# 03_Sensing.net
KiCad netlist of a schematic drawn in Altium Designer
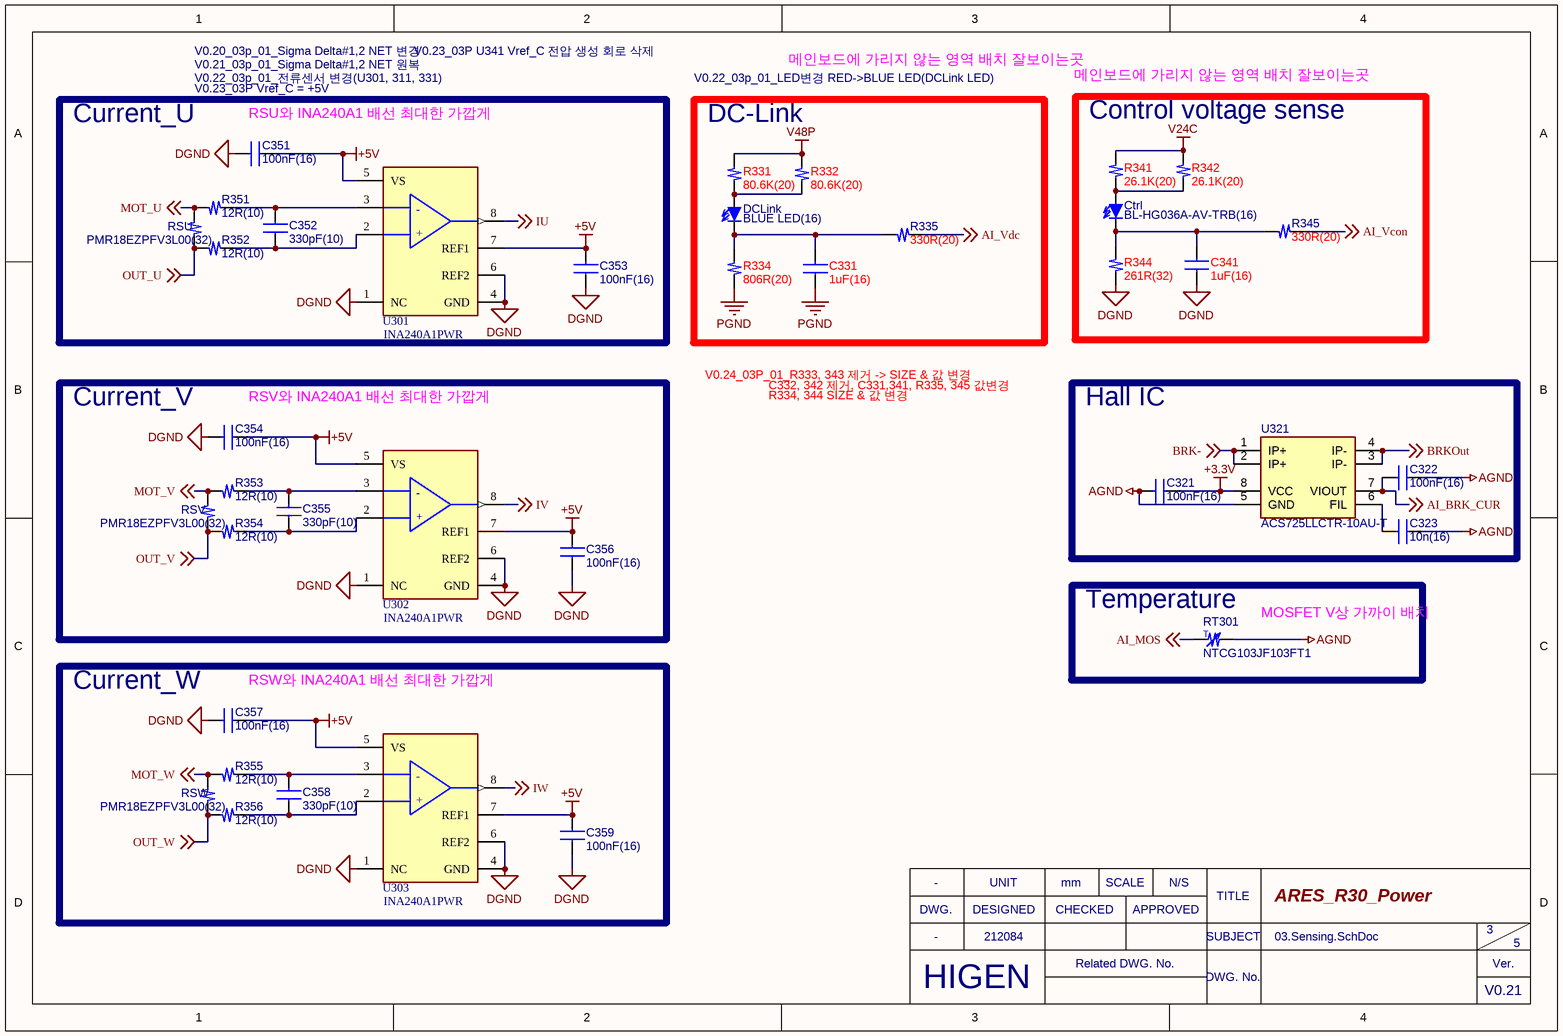
[diagram p0: 03.Sensing.SchDoc]

(export (version "E")
  (design (tool "Eeschema 10.0.6"))
  (components
    (comp (ref "C321") (value "100nF(16)") (footprint "C-1608S") (libsource (lib "HIGEN") (part "RES1")))
    (comp (ref "C322") (value "100nF(16)") (footprint "C-1608S") (libsource (lib "HIGEN") (part "RES1")))
    (comp (ref "C323") (value "10n(16)") (footprint "C-1608S") (libsource (lib "HIGEN") (part "Cap_NP")))
    (comp (ref "C331") (value "1uF(16)") (footprint "C-1608S") (libsource (lib "HIGEN") (part "RES1")))
    (comp (ref "C341") (value "1uF(16)") (footprint "C-1608S") (libsource (lib "HIGEN") (part "RES1")))
    (comp (ref "C351") (value "100nF(16)") (footprint "C-1608S") (libsource (lib "HIGEN") (part "RES1")))
    (comp (ref "C352") (value "330pF(10)") (footprint "C-1005S") (libsource (lib "HIGEN") (part "Cap_NP")))
    (comp (ref "C353") (value "100nF(16)") (footprint "C-1608") (libsource (lib "HIGEN") (part "Cap_NP")))
    (comp (ref "C354") (value "100nF(16)") (footprint "C-1608S") (libsource (lib "HIGEN") (part "RES1")))
    (comp (ref "C355") (value "330pF(10)") (footprint "C-1005S") (libsource (lib "HIGEN") (part "Cap_NP")))
    (comp (ref "C356") (value "100nF(16)") (footprint "C-1608") (libsource (lib "HIGEN") (part "Cap_NP")))
    (comp (ref "C357") (value "100nF(16)") (footprint "C-1608S") (libsource (lib "HIGEN") (part "RES1")))
    (comp (ref "C358") (value "330pF(10)") (footprint "C-1005S") (libsource (lib "HIGEN") (part "Cap_NP")))
    (comp (ref "C359") (value "100nF(16)") (footprint "C-1608") (libsource (lib "HIGEN") (part "Cap_NP")))
    (comp (ref "Ctrl")
      (value "BL-HG036A-AV-TRB(16)")
      (footprint "LED-1608-G")
      (libsource (lib "HIGEN") (part "LED"))
    )
    (comp (ref "DCLink")
      (value "BLUE LED(16)")
      (footprint "LED-1608-B")
      (libsource (lib "HIGEN") (part "LED"))
    )
    (comp (ref "R331") (value "80.6K(20)") (footprint "RES-2012") (libsource (lib "HIGEN") (part "Res")))
    (comp (ref "R332") (value "80.6K(20)") (footprint "RES-2012") (libsource (lib "HIGEN") (part "Res")))
    (comp (ref "R334") (value "806R(20)") (footprint "RES-2012") (libsource (lib "HIGEN") (part "Res")))
    (comp (ref "R335") (value "330R(20)") (footprint "RES-2012") (libsource (lib "HIGEN") (part "Res")))
    (comp (ref "R341") (value "26.1K(20)") (footprint "RES-2012") (libsource (lib "HIGEN") (part "Res")))
    (comp (ref "R342") (value "26.1K(20)") (footprint "RES-2012") (libsource (lib "HIGEN") (part "Res")))
    (comp (ref "R344") (value "261R(32)") (footprint "R-3216S") (libsource (lib "HIGEN") (part "Res")))
    (comp (ref "R345") (value "330R(20)") (footprint "RES-2012") (libsource (lib "HIGEN") (part "Res")))
    (comp (ref "R351") (value "12R(10)") (footprint "R-1005S") (libsource (lib "HIGEN") (part "Res")))
    (comp (ref "R352") (value "12R(10)") (footprint "R-1005S") (libsource (lib "HIGEN") (part "Res")))
    (comp (ref "R353") (value "12R(10)") (footprint "R-1005S") (libsource (lib "HIGEN") (part "Res")))
    (comp (ref "R354") (value "12R(10)") (footprint "R-1005S") (libsource (lib "HIGEN") (part "Res")))
    (comp (ref "R355") (value "12R(10)") (footprint "R-1005S") (libsource (lib "HIGEN") (part "Res")))
    (comp (ref "R356") (value "12R(10)") (footprint "R-1005S") (libsource (lib "HIGEN") (part "Res")))
    (comp (ref "RSU")
      (value "PMR18EZPFV3L00(32)")
      (footprint "R-5025")
      (libsource (lib "HIGEN") (part "Res"))
    )
    (comp (ref "RSV")
      (value "PMR18EZPFV3L00(32)")
      (footprint "R-5025")
      (libsource (lib "HIGEN") (part "Res"))
    )
    (comp (ref "RSW")
      (value "PMR18EZPFV3L00(32)")
      (footprint "R-5025")
      (libsource (lib "HIGEN") (part "Res"))
    )
    (comp (ref "RT301")
      (value "NTCG103JF103FT1")
      (footprint "L-1005")
      (libsource (lib "HIGEN") (part "Res_Thermal"))
    )
    (comp (ref "U301")
      (value "INA240A1PWR")
      (footprint "TSSOP-8")
      (description "IC CURR SENSE 1 CIRCUIT 8TSSOP")
      (fields
        (field (name "DIGIKEY PART NUMBER") "296-45088-1-ND")
        (field (name "MANUFACTURER") "Texas Instruments")
      )
      (libsource (lib "EEConcierge") (part "INA240A1PWR"))
    )
    (comp (ref "U302")
      (value "INA240A1PWR")
      (footprint "TSSOP-8")
      (description "IC CURR SENSE 1 CIRCUIT 8TSSOP")
      (fields
        (field (name "DIGIKEY PART NUMBER") "296-45088-1-ND")
        (field (name "MANUFACTURER") "Texas Instruments")
      )
      (libsource (lib "EEConcierge") (part "INA240A1PWR"))
    )
    (comp (ref "U303")
      (value "INA240A1PWR")
      (footprint "TSSOP-8")
      (description "IC CURR SENSE 1 CIRCUIT 8TSSOP")
      (fields
        (field (name "DIGIKEY PART NUMBER") "296-45088-1-ND")
        (field (name "MANUFACTURER") "Texas Instruments")
      )
      (libsource (lib "EEConcierge") (part "INA240A1PWR"))
    )
    (comp (ref "U321")
      (value "ACS725LLCTR-10AU-T")
      (footprint "SO-8")
      (libsource (lib "HIGEN") (part "ACS725LLCTR"))
    )
  )
  (nets
    (net (code "1") (name "+3.3V") (class "Default")
      (node (ref "C321") (pin "2") (pinfunction "2_2") (pintype "passive"))
      (node (ref "U321") (pin "8") (pinfunction "VCC_8") (pintype "passive"))
    )
    (net (code "2") (name "+5V") (class "Default")
      (node (ref "C351") (pin "1") (pinfunction "1_1") (pintype "passive"))
      (node (ref "C353") (pin "1") (pinfunction "1_1") (pintype "passive"))
      (node (ref "C354") (pin "1") (pinfunction "1_1") (pintype "passive"))
      (node (ref "C356") (pin "1") (pinfunction "1_1") (pintype "passive"))
      (node (ref "C357") (pin "1") (pinfunction "1_1") (pintype "passive"))
      (node (ref "C359") (pin "1") (pinfunction "1_1") (pintype "passive"))
      (node (ref "U301") (pin "5") (pinfunction "VS_5") (pintype "power_in"))
      (node (ref "U301") (pin "7") (pinfunction "REF1_7") (pintype "passive"))
      (node (ref "U302") (pin "5") (pinfunction "VS_5") (pintype "power_in"))
      (node (ref "U302") (pin "7") (pinfunction "REF1_7") (pintype "passive"))
      (node (ref "U303") (pin "5") (pinfunction "VS_5") (pintype "power_in"))
      (node (ref "U303") (pin "7") (pinfunction "REF1_7") (pintype "passive"))
    )
    (net (code "3") (name "AGND") (class "Default")
      (node (ref "C321") (pin "1") (pinfunction "1_1") (pintype "passive"))
      (node (ref "C322") (pin "2") (pinfunction "2_2") (pintype "passive"))
      (node (ref "C323") (pin "2") (pinfunction "2_2") (pintype "passive"))
      (node (ref "RT301") (pin "1") (pinfunction "1_1") (pintype "passive"))
      (node (ref "U321") (pin "5") (pinfunction "GND_5") (pintype "passive"))
    )
    (net (code "4") (name "AI_BRK_CUR") (class "Default")
      (node (ref "C322") (pin "1") (pinfunction "1_1") (pintype "passive"))
      (node (ref "U321") (pin "7") (pinfunction "VIOUT_7") (pintype "passive"))
    )
    (net (code "5") (name "AI_MOS") (class "Default")
      (node (ref "RT301") (pin "2") (pinfunction "2_2") (pintype "passive"))
    )
    (net (code "6") (name "AI_Vcon") (class "Default")
      (node (ref "R345") (pin "2") (pinfunction "P2_2") (pintype "passive"))
    )
    (net (code "7") (name "AI_Vdc") (class "Default")
      (node (ref "R335") (pin "2") (pinfunction "P2_2") (pintype "passive"))
    )
    (net (code "8") (name "BRK-") (class "Default")
      (node (ref "U321") (pin "1") (pinfunction "IP+_1") (pintype "passive"))
      (node (ref "U321") (pin "2") (pinfunction "IP+_2") (pintype "passive"))
    )
    (net (code "9") (name "BRKOut") (class "Default")
      (node (ref "U321") (pin "3") (pinfunction "IP-_3") (pintype "passive"))
      (node (ref "U321") (pin "4") (pinfunction "IP-_4") (pintype "passive"))
    )
    (net (code "10") (name "DGND") (class "Default")
      (node (ref "C341") (pin "2") (pinfunction "2_2") (pintype "passive"))
      (node (ref "C351") (pin "2") (pinfunction "2_2") (pintype "passive"))
      (node (ref "C353") (pin "2") (pinfunction "2_2") (pintype "passive"))
      (node (ref "C354") (pin "2") (pinfunction "2_2") (pintype "passive"))
      (node (ref "C356") (pin "2") (pinfunction "2_2") (pintype "passive"))
      (node (ref "C357") (pin "2") (pinfunction "2_2") (pintype "passive"))
      (node (ref "C359") (pin "2") (pinfunction "2_2") (pintype "passive"))
      (node (ref "R344") (pin "2") (pinfunction "P2_2") (pintype "passive"))
      (node (ref "U301") (pin "1") (pinfunction "NC_1") (pintype "passive"))
      (node (ref "U301") (pin "4") (pinfunction "GND_4") (pintype "power_in"))
      (node (ref "U301") (pin "6") (pinfunction "REF2_6") (pintype "passive"))
      (node (ref "U302") (pin "1") (pinfunction "NC_1") (pintype "passive"))
      (node (ref "U302") (pin "4") (pinfunction "GND_4") (pintype "power_in"))
      (node (ref "U302") (pin "6") (pinfunction "REF2_6") (pintype "passive"))
      (node (ref "U303") (pin "1") (pinfunction "NC_1") (pintype "passive"))
      (node (ref "U303") (pin "4") (pinfunction "GND_4") (pintype "power_in"))
      (node (ref "U303") (pin "6") (pinfunction "REF2_6") (pintype "passive"))
    )
    (net (code "11") (name "IU") (class "Default")
      (node (ref "U301") (pin "8") (pinfunction "OUT_8") (pintype "output"))
    )
    (net (code "12") (name "IV") (class "Default")
      (node (ref "U302") (pin "8") (pinfunction "OUT_8") (pintype "output"))
    )
    (net (code "13") (name "IW") (class "Default")
      (node (ref "U303") (pin "8") (pinfunction "OUT_8") (pintype "output"))
    )
    (net (code "14") (name "MOT_U") (class "Default")
      (node (ref "R351") (pin "1") (pinfunction "P1_1") (pintype "passive"))
      (node (ref "RSU") (pin "1") (pinfunction "P1_1") (pintype "passive"))
    )
    (net (code "15") (name "MOT_V") (class "Default")
      (node (ref "R353") (pin "1") (pinfunction "P1_1") (pintype "passive"))
      (node (ref "RSV") (pin "1") (pinfunction "P1_1") (pintype "passive"))
    )
    (net (code "16") (name "MOT_W") (class "Default")
      (node (ref "R355") (pin "1") (pinfunction "P1_1") (pintype "passive"))
      (node (ref "RSW") (pin "1") (pinfunction "P1_1") (pintype "passive"))
    )
    (net (code "17") (name "Net-(Ctrl-Anode)") (class "Default")
      (node (ref "Ctrl") (pin "1") (pinfunction "Anode_1") (pintype "passive"))
      (node (ref "R341") (pin "2") (pinfunction "P2_2") (pintype "passive"))
      (node (ref "R342") (pin "2") (pinfunction "P2_2") (pintype "passive"))
    )
    (net (code "18") (name "Net-(Ctrl-Cathode)") (class "Default")
      (node (ref "C341") (pin "1") (pinfunction "1_1") (pintype "passive"))
      (node (ref "Ctrl") (pin "2") (pinfunction "Cathode_2") (pintype "passive"))
      (node (ref "R344") (pin "1") (pinfunction "P1_1") (pintype "passive"))
      (node (ref "R345") (pin "1") (pinfunction "P1_1") (pintype "passive"))
    )
    (net (code "19") (name "Net-(DCLink-Anode)") (class "Default")
      (node (ref "DCLink") (pin "1") (pinfunction "Anode_1") (pintype "passive"))
      (node (ref "R331") (pin "2") (pinfunction "P2_2") (pintype "passive"))
      (node (ref "R332") (pin "2") (pinfunction "P2_2") (pintype "passive"))
    )
    (net (code "20") (name "Net-(DCLink-Cathode)") (class "Default")
      (node (ref "C331") (pin "1") (pinfunction "1_1") (pintype "passive"))
      (node (ref "DCLink") (pin "2") (pinfunction "Cathode_2") (pintype "passive"))
      (node (ref "R334") (pin "1") (pinfunction "P1_1") (pintype "passive"))
      (node (ref "R335") (pin "1") (pinfunction "P1_1") (pintype "passive"))
    )
    (net (code "21") (name "Net-(R351-P2)") (class "Default")
      (node (ref "C352") (pin "2") (pinfunction "2_2") (pintype "passive"))
      (node (ref "R351") (pin "2") (pinfunction "P2_2") (pintype "passive"))
      (node (ref "U301") (pin "3") (pinfunction "IN-_3") (pintype "tri_state"))
    )
    (net (code "22") (name "Net-(R352-P2)") (class "Default")
      (node (ref "C352") (pin "1") (pinfunction "1_1") (pintype "passive"))
      (node (ref "R352") (pin "2") (pinfunction "P2_2") (pintype "passive"))
      (node (ref "U301") (pin "2") (pinfunction "IN+_2") (pintype "tri_state"))
    )
    (net (code "23") (name "Net-(R353-P2)") (class "Default")
      (node (ref "C355") (pin "2") (pinfunction "2_2") (pintype "passive"))
      (node (ref "R353") (pin "2") (pinfunction "P2_2") (pintype "passive"))
      (node (ref "U302") (pin "3") (pinfunction "IN-_3") (pintype "tri_state"))
    )
    (net (code "24") (name "Net-(R354-P2)") (class "Default")
      (node (ref "C355") (pin "1") (pinfunction "1_1") (pintype "passive"))
      (node (ref "R354") (pin "2") (pinfunction "P2_2") (pintype "passive"))
      (node (ref "U302") (pin "2") (pinfunction "IN+_2") (pintype "tri_state"))
    )
    (net (code "25") (name "Net-(R355-P2)") (class "Default")
      (node (ref "C358") (pin "2") (pinfunction "2_2") (pintype "passive"))
      (node (ref "R355") (pin "2") (pinfunction "P2_2") (pintype "passive"))
      (node (ref "U303") (pin "3") (pinfunction "IN-_3") (pintype "tri_state"))
    )
    (net (code "26") (name "Net-(R356-P2)") (class "Default")
      (node (ref "C358") (pin "1") (pinfunction "1_1") (pintype "passive"))
      (node (ref "R356") (pin "2") (pinfunction "P2_2") (pintype "passive"))
      (node (ref "U303") (pin "2") (pinfunction "IN+_2") (pintype "tri_state"))
    )
    (net (code "27") (name "Net-(U321-FIL)") (class "Default")
      (node (ref "C323") (pin "1") (pinfunction "1_1") (pintype "passive"))
      (node (ref "U321") (pin "6") (pinfunction "FIL_6") (pintype "passive"))
    )
    (net (code "28") (name "OUT_U") (class "Default")
      (node (ref "R352") (pin "1") (pinfunction "P1_1") (pintype "passive"))
      (node (ref "RSU") (pin "2") (pinfunction "P2_2") (pintype "passive"))
    )
    (net (code "29") (name "OUT_V") (class "Default")
      (node (ref "R354") (pin "1") (pinfunction "P1_1") (pintype "passive"))
      (node (ref "RSV") (pin "2") (pinfunction "P2_2") (pintype "passive"))
    )
    (net (code "30") (name "OUT_W") (class "Default")
      (node (ref "R356") (pin "1") (pinfunction "P1_1") (pintype "passive"))
      (node (ref "RSW") (pin "2") (pinfunction "P2_2") (pintype "passive"))
    )
    (net (code "31") (name "PGND") (class "Default")
      (node (ref "C331") (pin "2") (pinfunction "2_2") (pintype "passive"))
      (node (ref "R334") (pin "2") (pinfunction "P2_2") (pintype "passive"))
    )
    (net (code "32") (name "V24C") (class "Default")
      (node (ref "R341") (pin "1") (pinfunction "P1_1") (pintype "passive"))
      (node (ref "R342") (pin "1") (pinfunction "P1_1") (pintype "passive"))
    )
    (net (code "33") (name "V48P") (class "Default")
      (node (ref "R331") (pin "1") (pinfunction "P1_1") (pintype "passive"))
      (node (ref "R332") (pin "1") (pinfunction "P1_1") (pintype "passive"))
    )
  )
)
